# SampIO.net
KiCad netlist of a schematic drawn in Altium Designer
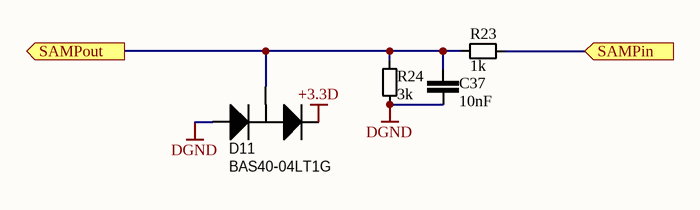
[diagram p0: SampIO.SchDoc]

(export (version "E")
  (design (tool "Eeschema 10.0.6"))
  (components
    (comp (ref "C37")
      (value "10nF")
      (footprint "GreenBox:0603-C")
      (description "MLCC 10nF 10% 50V X7R 0603")
      (fields (field (name "Comment") "Cap") (field (name "PUBLISHER") "GreenBox"))
      (libsource (lib "Capacitor") (part "C21C010NK1H0"))
    )
    (comp (ref "D11")
      (value "BAS40-04LT1G")
      (footprint "GreenBox:SOT-23_N")
      (description "Dual Series Schottky Barrier Diode BAS40-04LT1G Vrrm 40V If 0.12A Ir 1uA")
      (fields (field (name "MANUFACTURER") "ON SEMICONDUCTOR") (field (name "PUBLISHER") "GreenBox"))
      (libsource (lib "Diode_Transistor") (part "D742BAS4004O"))
    )
    (comp (ref "R23")
      (value "1k")
      (footprint "GreenBox:0603-R")
      (description "SMD Resistor 1k 1% 1/10W 0603 100PPM")
      (fields (field (name "Comment") "Res") (field (name "PUBLISHER") "GreenBox"))
      (libsource (lib "Resistor") (part "R11C001KFBF0"))
    )
    (comp (ref "R24")
      (value "3k")
      (footprint "GreenBox:0603-R")
      (description "SMD Resistor 3k 1% 1/10W 0603 100PPM")
      (fields (field (name "Comment") "Res") (field (name "PUBLISHER") "GreenBox"))
      (libsource (lib "Resistor") (part "R11C003KFBF0"))
    )
  )
  (nets
    (net (code "1") (name "+3.3D") (class "Default")
      (node (ref "D11") (pin "2") (pinfunction "K_2") (pintype "passive"))
    )
    (net (code "2") (name "/SAMPin") (class "Default")
      (node (ref "R23") (pin "2") (pinfunction "2_2") (pintype "passive"))
    )
    (net (code "3") (name "/SAMPout") (class "Default")
      (node (ref "C37") (pin "2") (pinfunction "2_2") (pintype "passive"))
      (node (ref "D11") (pin "3") (pinfunction "C_3") (pintype "passive"))
      (node (ref "R23") (pin "1") (pinfunction "1_1") (pintype "passive"))
      (node (ref "R24") (pin "2") (pinfunction "2_2") (pintype "passive"))
    )
    (net (code "4") (name "DGND") (class "Default")
      (node (ref "C37") (pin "1") (pinfunction "1_1") (pintype "passive"))
      (node (ref "D11") (pin "1") (pinfunction "A_1") (pintype "passive"))
      (node (ref "R24") (pin "1") (pinfunction "1_1") (pintype "passive"))
    )
  )
)
